# OpampTestBoard.net
KiCad netlist of a schematic drawn in EAGLE
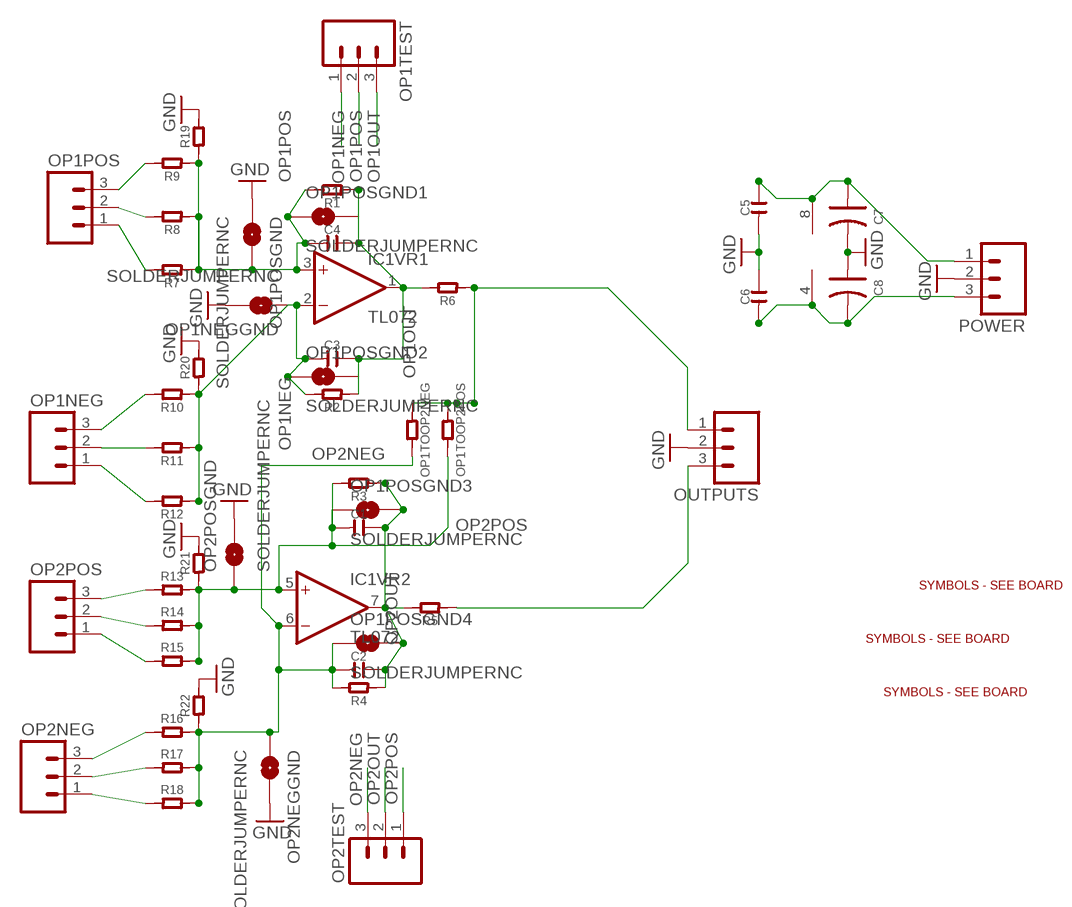
[diagram p0: schematic, sheet 1]

(export (version "E")
  (design (tool "Eeschema 10.0.6"))
  (components
    (comp (ref "C1")
      (value "C-0805")
      (footprint "eagle-import:C0805")
      (libsource (lib "eagle-import") (part "C-0805"))
    )
    (comp (ref "C2")
      (value "C-0805")
      (footprint "eagle-import:C0805")
      (libsource (lib "eagle-import") (part "C-0805"))
    )
    (comp (ref "C3")
      (value "C-0805")
      (footprint "eagle-import:C0805")
      (libsource (lib "eagle-import") (part "C-0805"))
    )
    (comp (ref "C4")
      (value "C-0805")
      (footprint "eagle-import:C0805")
      (libsource (lib "eagle-import") (part "C-0805"))
    )
    (comp (ref "C5")
      (value "C-0805")
      (footprint "eagle-import:C0805")
      (libsource (lib "eagle-import") (part "C-0805"))
    )
    (comp (ref "C6")
      (value "C-0805")
      (footprint "eagle-import:C0805")
      (libsource (lib "eagle-import") (part "C-0805"))
    )
    (comp (ref "C7")
      (value "C-POLAR-A")
      (footprint "eagle-import:AVX-A")
      (libsource (lib "eagle-import") (part "C-POLAR-A"))
    )
    (comp (ref "C8")
      (value "C-POLAR-A")
      (footprint "eagle-import:AVX-A")
      (libsource (lib "eagle-import") (part "C-POLAR-A"))
    )
    (comp (ref "IC1")
      (value "TL072")
      (footprint "eagle-import:SO08")
      (libsource (lib "eagle-import") (part "TL072"))
    )
    (comp (ref "OP1NEG")
      (value "M03PTH")
      (footprint "eagle-import:1X03")
      (libsource (lib "eagle-import") (part "M03PTH"))
    )
    (comp (ref "OP1NEGGND")
      (value "SOLDERJUMPERNC")
      (footprint "eagle-import:SJ_2S")
      (libsource (lib "eagle-import") (part "SOLDERJUMPERNC"))
    )
    (comp (ref "OP1POS")
      (value "M03PTH")
      (footprint "eagle-import:1X03")
      (libsource (lib "eagle-import") (part "M03PTH"))
    )
    (comp (ref "OP1POSGND")
      (value "SOLDERJUMPERNC")
      (footprint "eagle-import:SJ_2S")
      (libsource (lib "eagle-import") (part "SOLDERJUMPERNC"))
    )
    (comp (ref "OP1POSGND1")
      (value "SOLDERJUMPERNC")
      (footprint "eagle-import:SJ_2S")
      (libsource (lib "eagle-import") (part "SOLDERJUMPERNC"))
    )
    (comp (ref "OP1POSGND2")
      (value "SOLDERJUMPERNC")
      (footprint "eagle-import:SJ_2S")
      (libsource (lib "eagle-import") (part "SOLDERJUMPERNC"))
    )
    (comp (ref "OP1POSGND3")
      (value "SOLDERJUMPERNC")
      (footprint "eagle-import:SJ_2S")
      (libsource (lib "eagle-import") (part "SOLDERJUMPERNC"))
    )
    (comp (ref "OP1POSGND4")
      (value "SOLDERJUMPERNC")
      (footprint "eagle-import:SJ_2S")
      (libsource (lib "eagle-import") (part "SOLDERJUMPERNC"))
    )
    (comp (ref "OP1TEST")
      (value "M03PTH")
      (footprint "eagle-import:1X03")
      (libsource (lib "eagle-import") (part "M03PTH"))
    )
    (comp (ref "OP1TOOP2NEG")
      (value "R-0603")
      (footprint "eagle-import:R0603")
      (libsource (lib "eagle-import") (part "R-0603"))
    )
    (comp (ref "OP1TOOP2POS")
      (value "R-0603")
      (footprint "eagle-import:R0603")
      (libsource (lib "eagle-import") (part "R-0603"))
    )
    (comp (ref "OP2NEG")
      (value "M03PTH")
      (footprint "eagle-import:1X03")
      (libsource (lib "eagle-import") (part "M03PTH"))
    )
    (comp (ref "OP2NEGGND")
      (value "SOLDERJUMPERNC")
      (footprint "eagle-import:SJ_2S")
      (libsource (lib "eagle-import") (part "SOLDERJUMPERNC"))
    )
    (comp (ref "OP2POS")
      (value "M03PTH")
      (footprint "eagle-import:1X03")
      (libsource (lib "eagle-import") (part "M03PTH"))
    )
    (comp (ref "OP2POSGND")
      (value "SOLDERJUMPERNC")
      (footprint "eagle-import:SJ_2S")
      (libsource (lib "eagle-import") (part "SOLDERJUMPERNC"))
    )
    (comp (ref "OP2TEST")
      (value "M03PTH")
      (footprint "eagle-import:1X03")
      (libsource (lib "eagle-import") (part "M03PTH"))
    )
    (comp (ref "OUTPUTS")
      (value "M03PTH")
      (footprint "eagle-import:1X03")
      (libsource (lib "eagle-import") (part "M03PTH"))
    )
    (comp (ref "POWER")
      (value "M03PTH")
      (footprint "eagle-import:1X03")
      (libsource (lib "eagle-import") (part "M03PTH"))
    )
    (comp (ref "R1")
      (value "R-0603")
      (footprint "eagle-import:R0603")
      (libsource (lib "eagle-import") (part "R-0603"))
    )
    (comp (ref "R2")
      (value "R-0603")
      (footprint "eagle-import:R0603")
      (libsource (lib "eagle-import") (part "R-0603"))
    )
    (comp (ref "R3")
      (value "R-0603")
      (footprint "eagle-import:R0603")
      (libsource (lib "eagle-import") (part "R-0603"))
    )
    (comp (ref "R4")
      (value "R-0603")
      (footprint "eagle-import:R0603")
      (libsource (lib "eagle-import") (part "R-0603"))
    )
    (comp (ref "R5")
      (value "R-0603")
      (footprint "eagle-import:R0603")
      (libsource (lib "eagle-import") (part "R-0603"))
    )
    (comp (ref "R6")
      (value "R-0603")
      (footprint "eagle-import:R0603")
      (libsource (lib "eagle-import") (part "R-0603"))
    )
    (comp (ref "R7")
      (value "R-0603")
      (footprint "eagle-import:R0603")
      (libsource (lib "eagle-import") (part "R-0603"))
    )
    (comp (ref "R8")
      (value "R-0603")
      (footprint "eagle-import:R0603")
      (libsource (lib "eagle-import") (part "R-0603"))
    )
    (comp (ref "R9")
      (value "R-0603")
      (footprint "eagle-import:R0603")
      (libsource (lib "eagle-import") (part "R-0603"))
    )
    (comp (ref "R10")
      (value "R-0603")
      (footprint "eagle-import:R0603")
      (libsource (lib "eagle-import") (part "R-0603"))
    )
    (comp (ref "R11")
      (value "R-0603")
      (footprint "eagle-import:R0603")
      (libsource (lib "eagle-import") (part "R-0603"))
    )
    (comp (ref "R12")
      (value "R-0603")
      (footprint "eagle-import:R0603")
      (libsource (lib "eagle-import") (part "R-0603"))
    )
    (comp (ref "R13")
      (value "R-0603")
      (footprint "eagle-import:R0603")
      (libsource (lib "eagle-import") (part "R-0603"))
    )
    (comp (ref "R14")
      (value "R-0603")
      (footprint "eagle-import:R0603")
      (libsource (lib "eagle-import") (part "R-0603"))
    )
    (comp (ref "R15")
      (value "R-0603")
      (footprint "eagle-import:R0603")
      (libsource (lib "eagle-import") (part "R-0603"))
    )
    (comp (ref "R16")
      (value "R-0603")
      (footprint "eagle-import:R0603")
      (libsource (lib "eagle-import") (part "R-0603"))
    )
    (comp (ref "R17")
      (value "R-0603")
      (footprint "eagle-import:R0603")
      (libsource (lib "eagle-import") (part "R-0603"))
    )
    (comp (ref "R18")
      (value "R-0603")
      (footprint "eagle-import:R0603")
      (libsource (lib "eagle-import") (part "R-0603"))
    )
    (comp (ref "R19")
      (value "R-0603")
      (footprint "eagle-import:R0603")
      (libsource (lib "eagle-import") (part "R-0603"))
    )
    (comp (ref "R20")
      (value "R-0603")
      (footprint "eagle-import:R0603")
      (libsource (lib "eagle-import") (part "R-0603"))
    )
    (comp (ref "R21")
      (value "R-0603")
      (footprint "eagle-import:R0603")
      (libsource (lib "eagle-import") (part "R-0603"))
    )
    (comp (ref "R22")
      (value "R-0603")
      (footprint "eagle-import:R0603")
      (libsource (lib "eagle-import") (part "R-0603"))
    )
    (comp (ref "U$1")
      (value "SYMBOLSOPAMP")
      (footprint "eagle-import:SYMB_OPAMP")
      (libsource (lib "eagle-import") (part "SYMBOLSOPAMP"))
    )
    (comp (ref "U$2")
      (value "R2")
      (footprint "eagle-import:RESISTOR")
      (libsource (lib "eagle-import") (part "SYMBOLSRESISTOR"))
    )
    (comp (ref "U$3")
      (value "R1")
      (footprint "eagle-import:RESISTOR")
      (libsource (lib "eagle-import") (part "SYMBOLSRESISTOR"))
    )
  )
  (nets
    (net (code "1") (name "/OP1NEG") (class "Default")
      (node (ref "C3") (pin "1") (pinfunction "1_1") (pintype "bidirectional"))
      (node (ref "IC1") (pin "2") (pinfunction "-IN_2") (pintype "input"))
      (node (ref "OP1NEGGND") (pin "1") (pinfunction "1_1") (pintype "passive"))
      (node (ref "OP1POSGND2") (pin "1") (pinfunction "1_1") (pintype "passive"))
      (node (ref "OP1TEST") (pin "1") (pinfunction "1_1") (pintype "passive"))
      (node (ref "R10") (pin "1") (pinfunction "1_1") (pintype "bidirectional"))
      (node (ref "R11") (pin "1") (pinfunction "1_1") (pintype "bidirectional"))
      (node (ref "R12") (pin "1") (pinfunction "1_1") (pintype "bidirectional"))
      (node (ref "R2") (pin "2") (pinfunction "2_2") (pintype "bidirectional"))
      (node (ref "R20") (pin "1") (pinfunction "1_1") (pintype "bidirectional"))
    )
    (net (code "2") (name "/OP1OUT") (class "Default")
      (node (ref "C3") (pin "2") (pinfunction "2_2") (pintype "bidirectional"))
      (node (ref "C4") (pin "2") (pinfunction "2_2") (pintype "bidirectional"))
      (node (ref "IC1") (pin "1") (pinfunction "OUT_1") (pintype "output"))
      (node (ref "OP1POSGND1") (pin "2") (pinfunction "2_2") (pintype "passive"))
      (node (ref "OP1POSGND2") (pin "2") (pinfunction "2_2") (pintype "passive"))
      (node (ref "OP1TEST") (pin "3") (pinfunction "3_3") (pintype "passive"))
      (node (ref "R1") (pin "1") (pinfunction "1_1") (pintype "bidirectional"))
      (node (ref "R2") (pin "1") (pinfunction "1_1") (pintype "bidirectional"))
      (node (ref "R6") (pin "2") (pinfunction "2_2") (pintype "bidirectional"))
    )
    (net (code "3") (name "/OP1POS") (class "Default")
      (node (ref "C4") (pin "1") (pinfunction "1_1") (pintype "bidirectional"))
      (node (ref "IC1") (pin "3") (pinfunction "+IN_3") (pintype "input"))
      (node (ref "OP1POSGND") (pin "2") (pinfunction "2_2") (pintype "passive"))
      (node (ref "OP1POSGND1") (pin "1") (pinfunction "1_1") (pintype "passive"))
      (node (ref "OP1TEST") (pin "2") (pinfunction "2_2") (pintype "passive"))
      (node (ref "R1") (pin "2") (pinfunction "2_2") (pintype "bidirectional"))
      (node (ref "R19") (pin "1") (pinfunction "1_1") (pintype "bidirectional"))
      (node (ref "R7") (pin "1") (pinfunction "1_1") (pintype "bidirectional"))
      (node (ref "R8") (pin "1") (pinfunction "1_1") (pintype "bidirectional"))
      (node (ref "R9") (pin "1") (pinfunction "1_1") (pintype "bidirectional"))
    )
    (net (code "4") (name "/OP2NEG") (class "Default")
      (node (ref "C2") (pin "1") (pinfunction "1_1") (pintype "bidirectional"))
      (node (ref "IC1") (pin "6") (pinfunction "-IN_6") (pintype "input"))
      (node (ref "OP1POSGND4") (pin "1") (pinfunction "1_1") (pintype "passive"))
      (node (ref "OP1TOOP2NEG") (pin "2") (pinfunction "2_2") (pintype "bidirectional"))
      (node (ref "OP2NEGGND") (pin "1") (pinfunction "1_1") (pintype "passive"))
      (node (ref "OP2TEST") (pin "3") (pinfunction "3_3") (pintype "passive"))
      (node (ref "R16") (pin "2") (pinfunction "2_2") (pintype "bidirectional"))
      (node (ref "R17") (pin "2") (pinfunction "2_2") (pintype "bidirectional"))
      (node (ref "R18") (pin "2") (pinfunction "2_2") (pintype "bidirectional"))
      (node (ref "R22") (pin "1") (pinfunction "1_1") (pintype "bidirectional"))
      (node (ref "R4") (pin "2") (pinfunction "2_2") (pintype "bidirectional"))
    )
    (net (code "5") (name "/OP2OUT") (class "Default")
      (node (ref "C1") (pin "2") (pinfunction "2_2") (pintype "bidirectional"))
      (node (ref "C2") (pin "2") (pinfunction "2_2") (pintype "bidirectional"))
      (node (ref "IC1") (pin "7") (pinfunction "OUT_7") (pintype "output"))
      (node (ref "OP1POSGND3") (pin "2") (pinfunction "2_2") (pintype "passive"))
      (node (ref "OP1POSGND4") (pin "2") (pinfunction "2_2") (pintype "passive"))
      (node (ref "OP2TEST") (pin "2") (pinfunction "2_2") (pintype "passive"))
      (node (ref "R3") (pin "1") (pinfunction "1_1") (pintype "bidirectional"))
      (node (ref "R4") (pin "1") (pinfunction "1_1") (pintype "bidirectional"))
      (node (ref "R5") (pin "2") (pinfunction "2_2") (pintype "bidirectional"))
    )
    (net (code "6") (name "/OP2POS") (class "Default")
      (node (ref "C1") (pin "1") (pinfunction "1_1") (pintype "bidirectional"))
      (node (ref "IC1") (pin "5") (pinfunction "+IN_5") (pintype "input"))
      (node (ref "OP1POSGND3") (pin "1") (pinfunction "1_1") (pintype "passive"))
      (node (ref "OP1TOOP2POS") (pin "2") (pinfunction "2_2") (pintype "bidirectional"))
      (node (ref "OP2POSGND") (pin "1") (pinfunction "1_1") (pintype "passive"))
      (node (ref "OP2TEST") (pin "1") (pinfunction "1_1") (pintype "passive"))
      (node (ref "R13") (pin "2") (pinfunction "2_2") (pintype "bidirectional"))
      (node (ref "R14") (pin "2") (pinfunction "2_2") (pintype "bidirectional"))
      (node (ref "R15") (pin "2") (pinfunction "2_2") (pintype "bidirectional"))
      (node (ref "R21") (pin "1") (pinfunction "1_1") (pintype "bidirectional"))
      (node (ref "R3") (pin "2") (pinfunction "2_2") (pintype "bidirectional"))
    )
    (net (code "7") (name "GND") (class "Default")
      (node (ref "C5") (pin "1") (pinfunction "1_1") (pintype "bidirectional"))
      (node (ref "C6") (pin "2") (pinfunction "2_2") (pintype "bidirectional"))
      (node (ref "C7") (pin "-") (pinfunction "2_-") (pintype "bidirectional"))
      (node (ref "C8") (pin "+") (pinfunction "1_+") (pintype "bidirectional"))
      (node (ref "OP1NEGGND") (pin "2") (pinfunction "2_2") (pintype "passive"))
      (node (ref "OP1POSGND") (pin "1") (pinfunction "1_1") (pintype "passive"))
      (node (ref "OP2NEGGND") (pin "2") (pinfunction "2_2") (pintype "passive"))
      (node (ref "OP2POSGND") (pin "2") (pinfunction "2_2") (pintype "passive"))
      (node (ref "OUTPUTS") (pin "2") (pinfunction "2_2") (pintype "passive"))
      (node (ref "POWER") (pin "2") (pinfunction "2_2") (pintype "passive"))
      (node (ref "R19") (pin "2") (pinfunction "2_2") (pintype "bidirectional"))
      (node (ref "R20") (pin "2") (pinfunction "2_2") (pintype "bidirectional"))
      (node (ref "R21") (pin "2") (pinfunction "2_2") (pintype "bidirectional"))
      (node (ref "R22") (pin "2") (pinfunction "2_2") (pintype "bidirectional"))
    )
    (net (code "8") (name "Net-(C7-1)") (class "Default")
      (node (ref "C5") (pin "2") (pinfunction "2_2") (pintype "bidirectional"))
      (node (ref "C7") (pin "+") (pinfunction "1_+") (pintype "bidirectional"))
      (node (ref "IC1") (pin "8") (pinfunction "V+_8") (pintype "power_in"))
      (node (ref "POWER") (pin "1") (pinfunction "1_1") (pintype "passive"))
    )
    (net (code "9") (name "Net-(C8-2)") (class "Default")
      (node (ref "C6") (pin "1") (pinfunction "1_1") (pintype "bidirectional"))
      (node (ref "C8") (pin "-") (pinfunction "2_-") (pintype "bidirectional"))
      (node (ref "IC1") (pin "4") (pinfunction "V-_4") (pintype "power_in"))
      (node (ref "POWER") (pin "3") (pinfunction "3_3") (pintype "passive"))
    )
    (net (code "10") (name "Net-(OP1NEG-Pad1)") (class "Default")
      (node (ref "OP1NEG") (pin "1") (pinfunction "1_1") (pintype "passive"))
      (node (ref "R12") (pin "2") (pinfunction "2_2") (pintype "bidirectional"))
    )
    (net (code "11") (name "Net-(OP1NEG-Pad2)") (class "Default")
      (node (ref "OP1NEG") (pin "2") (pinfunction "2_2") (pintype "passive"))
      (node (ref "R11") (pin "2") (pinfunction "2_2") (pintype "bidirectional"))
    )
    (net (code "12") (name "Net-(OP1NEG-Pad3)") (class "Default")
      (node (ref "OP1NEG") (pin "3") (pinfunction "3_3") (pintype "passive"))
      (node (ref "R10") (pin "2") (pinfunction "2_2") (pintype "bidirectional"))
    )
    (net (code "13") (name "Net-(OP1POS-Pad1)") (class "Default")
      (node (ref "OP1POS") (pin "1") (pinfunction "1_1") (pintype "passive"))
      (node (ref "R7") (pin "2") (pinfunction "2_2") (pintype "bidirectional"))
    )
    (net (code "14") (name "Net-(OP1POS-Pad2)") (class "Default")
      (node (ref "OP1POS") (pin "2") (pinfunction "2_2") (pintype "passive"))
      (node (ref "R8") (pin "2") (pinfunction "2_2") (pintype "bidirectional"))
    )
    (net (code "15") (name "Net-(OP1POS-Pad3)") (class "Default")
      (node (ref "OP1POS") (pin "3") (pinfunction "3_3") (pintype "passive"))
      (node (ref "R9") (pin "2") (pinfunction "2_2") (pintype "bidirectional"))
    )
    (net (code "16") (name "Net-(OP1TOOP2NEG-Pad1)") (class "Default")
      (node (ref "OP1TOOP2NEG") (pin "1") (pinfunction "1_1") (pintype "bidirectional"))
      (node (ref "OP1TOOP2POS") (pin "1") (pinfunction "1_1") (pintype "bidirectional"))
      (node (ref "OUTPUTS") (pin "1") (pinfunction "1_1") (pintype "passive"))
      (node (ref "R6") (pin "1") (pinfunction "1_1") (pintype "bidirectional"))
    )
    (net (code "17") (name "Net-(OP2NEG-Pad1)") (class "Default")
      (node (ref "OP2NEG") (pin "1") (pinfunction "1_1") (pintype "passive"))
      (node (ref "R18") (pin "1") (pinfunction "1_1") (pintype "bidirectional"))
    )
    (net (code "18") (name "Net-(OP2NEG-Pad2)") (class "Default")
      (node (ref "OP2NEG") (pin "2") (pinfunction "2_2") (pintype "passive"))
      (node (ref "R17") (pin "1") (pinfunction "1_1") (pintype "bidirectional"))
    )
    (net (code "19") (name "Net-(OP2NEG-Pad3)") (class "Default")
      (node (ref "OP2NEG") (pin "3") (pinfunction "3_3") (pintype "passive"))
      (node (ref "R16") (pin "1") (pinfunction "1_1") (pintype "bidirectional"))
    )
    (net (code "20") (name "Net-(OP2POS-Pad1)") (class "Default")
      (node (ref "OP2POS") (pin "1") (pinfunction "1_1") (pintype "passive"))
      (node (ref "R15") (pin "1") (pinfunction "1_1") (pintype "bidirectional"))
    )
    (net (code "21") (name "Net-(OP2POS-Pad2)") (class "Default")
      (node (ref "OP2POS") (pin "2") (pinfunction "2_2") (pintype "passive"))
      (node (ref "R14") (pin "1") (pinfunction "1_1") (pintype "bidirectional"))
    )
    (net (code "22") (name "Net-(OP2POS-Pad3)") (class "Default")
      (node (ref "OP2POS") (pin "3") (pinfunction "3_3") (pintype "passive"))
      (node (ref "R13") (pin "1") (pinfunction "1_1") (pintype "bidirectional"))
    )
    (net (code "23") (name "Net-(OUTPUTS-Pad3)") (class "Default")
      (node (ref "OUTPUTS") (pin "3") (pinfunction "3_3") (pintype "passive"))
      (node (ref "R5") (pin "1") (pinfunction "1_1") (pintype "bidirectional"))
    )
  )
)
